# esc_board1.net
KiCad netlist of a schematic drawn in EAGLE
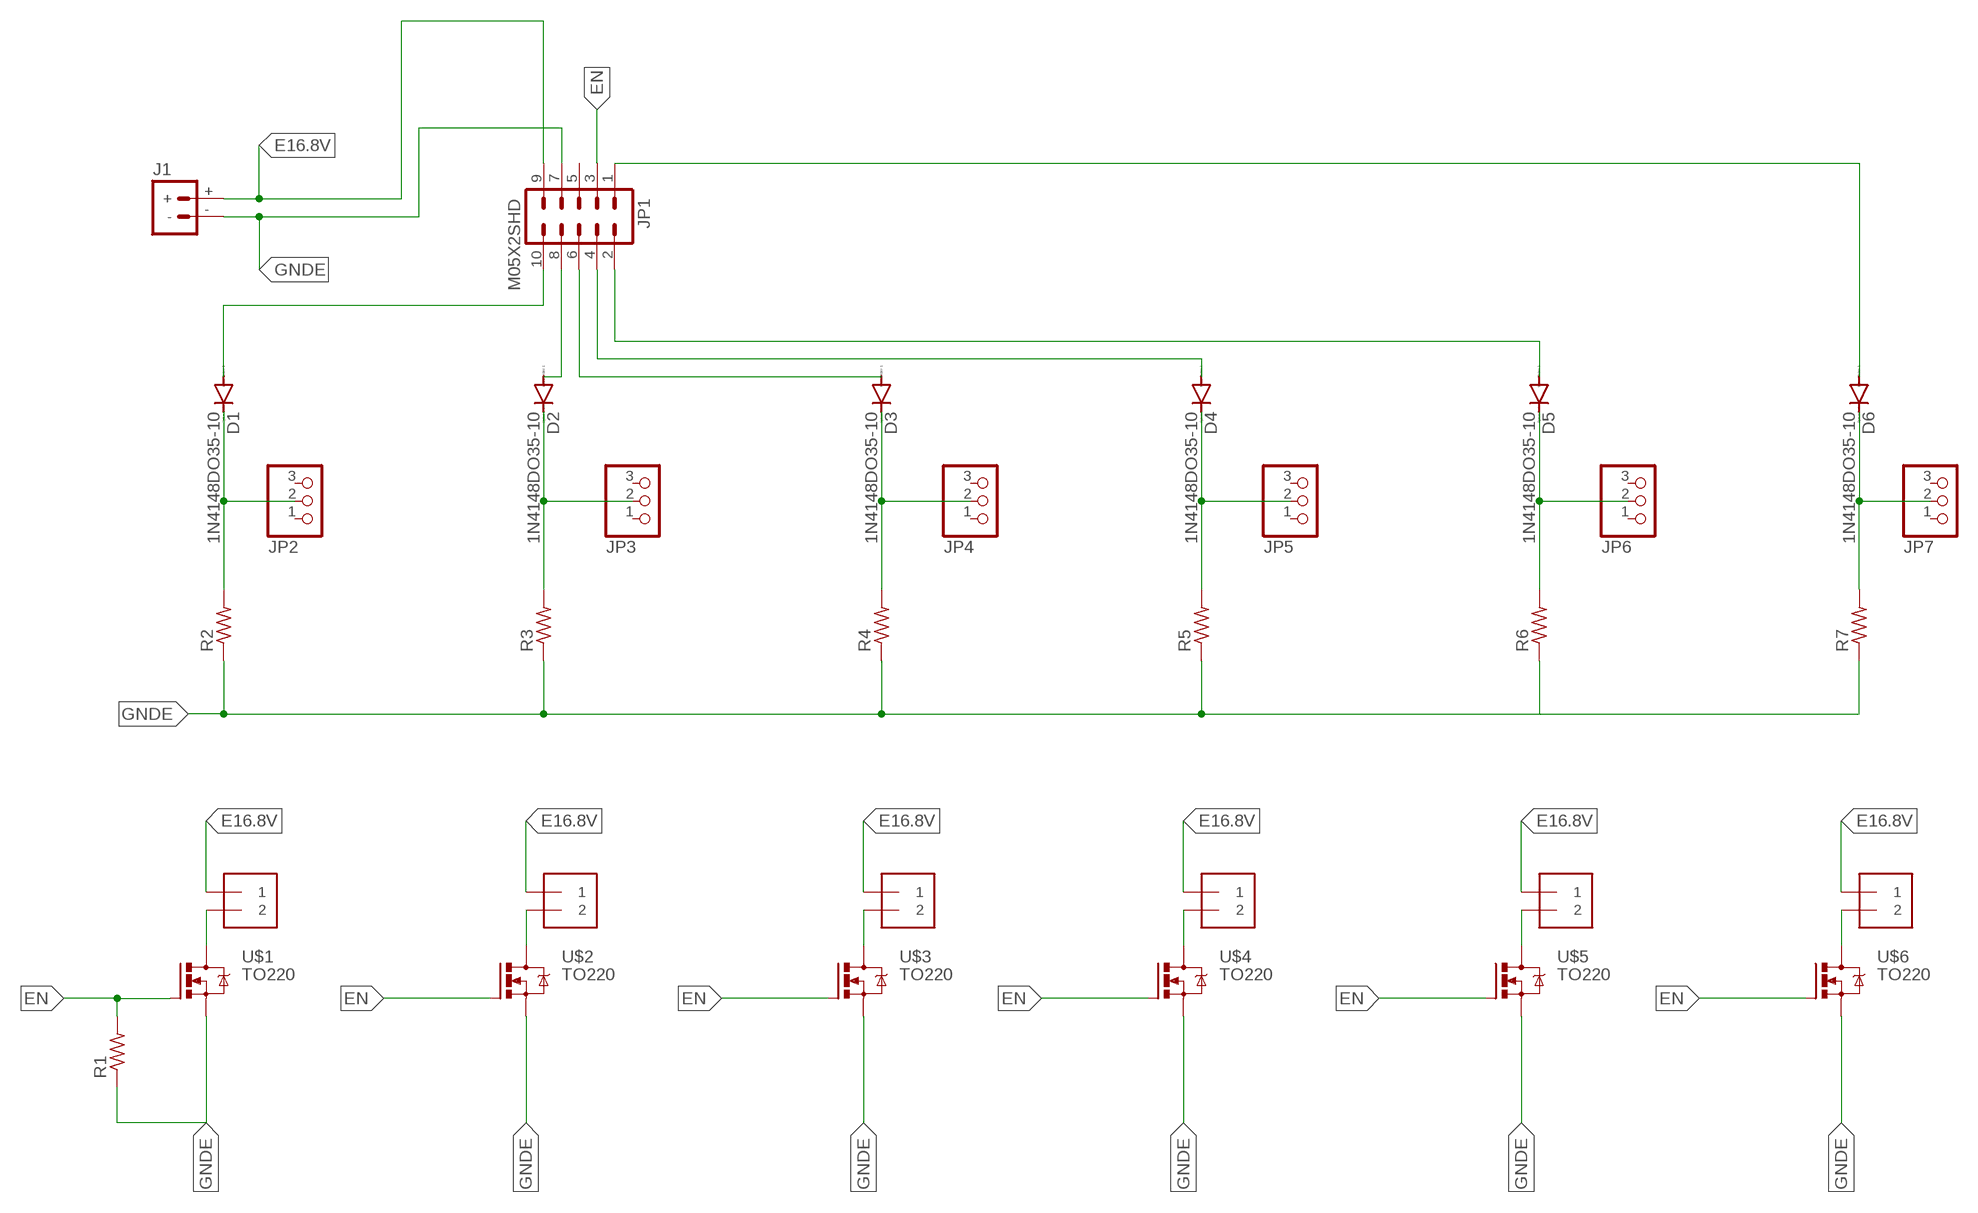
[diagram p0: schematic, sheet 1]

(export (version "E")
  (design (tool "Eeschema 10.0.6"))
  (components
    (comp (ref "D1")
      (value "1N4148DO35-10")
      (footprint "eagle-import:DO35-10")
      (libsource (lib "eagle-import") (part "1N4148DO35-10"))
    )
    (comp (ref "D2")
      (value "1N4148DO35-10")
      (footprint "eagle-import:DO35-10")
      (libsource (lib "eagle-import") (part "1N4148DO35-10"))
    )
    (comp (ref "D3")
      (value "1N4148DO35-10")
      (footprint "eagle-import:DO35-10")
      (libsource (lib "eagle-import") (part "1N4148DO35-10"))
    )
    (comp (ref "D4")
      (value "1N4148DO35-10")
      (footprint "eagle-import:DO35-10")
      (libsource (lib "eagle-import") (part "1N4148DO35-10"))
    )
    (comp (ref "D5")
      (value "1N4148DO35-10")
      (footprint "eagle-import:DO35-10")
      (libsource (lib "eagle-import") (part "1N4148DO35-10"))
    )
    (comp (ref "D6")
      (value "1N4148DO35-10")
      (footprint "eagle-import:DO35-10")
      (libsource (lib "eagle-import") (part "1N4148DO35-10"))
    )
    (comp (ref "J1")
      (value "BATTERY_CONN_DEANS")
      (footprint "eagle-import:DEANS")
      (libsource (lib "eagle-import") (part "BATTERY_CONN_DEANS"))
    )
    (comp (ref "J7")
      (value "1X2-3.5MM")
      (footprint "eagle-import:1X2-3.5MM")
      (libsource (lib "eagle-import") (part "1X2-3.5MM"))
    )
    (comp (ref "J8")
      (value "1X2-3.5MM")
      (footprint "eagle-import:1X2-3.5MM")
      (libsource (lib "eagle-import") (part "1X2-3.5MM"))
    )
    (comp (ref "J9")
      (value "1X2-3.5MM")
      (footprint "eagle-import:1X2-3.5MM")
      (libsource (lib "eagle-import") (part "1X2-3.5MM"))
    )
    (comp (ref "J10")
      (value "1X2-3.5MM")
      (footprint "eagle-import:1X2-3.5MM")
      (libsource (lib "eagle-import") (part "1X2-3.5MM"))
    )
    (comp (ref "J11")
      (value "1X2-3.5MM")
      (footprint "eagle-import:1X2-3.5MM")
      (libsource (lib "eagle-import") (part "1X2-3.5MM"))
    )
    (comp (ref "J12")
      (value "1X2-3.5MM")
      (footprint "eagle-import:1X2-3.5MM")
      (libsource (lib "eagle-import") (part "1X2-3.5MM"))
    )
    (comp (ref "JP1")
      (value "M05X2SHD")
      (footprint "eagle-import:2X5-SHROUDED")
      (libsource (lib "eagle-import") (part "M05X2SHD"))
    )
    (comp (ref "JP2")
      (value "PINHD-1X3")
      (footprint "eagle-import:1X03")
      (libsource (lib "eagle-import") (part "PINHD-1X3"))
    )
    (comp (ref "JP3")
      (value "PINHD-1X3")
      (footprint "eagle-import:1X03")
      (libsource (lib "eagle-import") (part "PINHD-1X3"))
    )
    (comp (ref "JP4")
      (value "PINHD-1X3")
      (footprint "eagle-import:1X03")
      (libsource (lib "eagle-import") (part "PINHD-1X3"))
    )
    (comp (ref "JP5")
      (value "PINHD-1X3")
      (footprint "eagle-import:1X03")
      (libsource (lib "eagle-import") (part "PINHD-1X3"))
    )
    (comp (ref "JP6")
      (value "PINHD-1X3")
      (footprint "eagle-import:1X03")
      (libsource (lib "eagle-import") (part "PINHD-1X3"))
    )
    (comp (ref "JP7")
      (value "PINHD-1X3")
      (footprint "eagle-import:1X03")
      (libsource (lib "eagle-import") (part "PINHD-1X3"))
    )
    (comp (ref "R1")
      (value "R-US_0204/7")
      (footprint "eagle-import:0204_7")
      (libsource (lib "eagle-import") (part "R-US_0204/7"))
    )
    (comp (ref "R2")
      (value "R-US_0204/7")
      (footprint "eagle-import:0204_7")
      (libsource (lib "eagle-import") (part "R-US_0204/7"))
    )
    (comp (ref "R3")
      (value "R-US_0204/7")
      (footprint "eagle-import:0204_7")
      (libsource (lib "eagle-import") (part "R-US_0204/7"))
    )
    (comp (ref "R4")
      (value "R-US_0204/7")
      (footprint "eagle-import:0204_7")
      (libsource (lib "eagle-import") (part "R-US_0204/7"))
    )
    (comp (ref "R5")
      (value "R-US_0204/7")
      (footprint "eagle-import:0204_7")
      (libsource (lib "eagle-import") (part "R-US_0204/7"))
    )
    (comp (ref "R6")
      (value "R-US_0204/7")
      (footprint "eagle-import:0204_7")
      (libsource (lib "eagle-import") (part "R-US_0204/7"))
    )
    (comp (ref "R7")
      (value "R-US_0204/7")
      (footprint "eagle-import:0204_7")
      (libsource (lib "eagle-import") (part "R-US_0204/7"))
    )
    (comp (ref "U$1")
      (value "TO220")
      (footprint "eagle-import:IRF540")
      (libsource (lib "eagle-import") (part "TO220"))
    )
    (comp (ref "U$2")
      (value "TO220")
      (footprint "eagle-import:IRF540")
      (libsource (lib "eagle-import") (part "TO220"))
    )
    (comp (ref "U$3")
      (value "TO220")
      (footprint "eagle-import:IRF540")
      (libsource (lib "eagle-import") (part "TO220"))
    )
    (comp (ref "U$4")
      (value "TO220")
      (footprint "eagle-import:IRF540")
      (libsource (lib "eagle-import") (part "TO220"))
    )
    (comp (ref "U$5")
      (value "TO220")
      (footprint "eagle-import:IRF540")
      (libsource (lib "eagle-import") (part "TO220"))
    )
    (comp (ref "U$6")
      (value "TO220")
      (footprint "eagle-import:IRF540")
      (libsource (lib "eagle-import") (part "TO220"))
    )
  )
  (nets
    (net (code "1") (name "E16.8V") (class "Default")
      (node (ref "J1") (pin "+") (pinfunction "+_+") (pintype "passive"))
      (node (ref "J10") (pin "1") (pinfunction "1_1") (pintype "passive"))
      (node (ref "J11") (pin "1") (pinfunction "1_1") (pintype "passive"))
      (node (ref "J12") (pin "1") (pinfunction "1_1") (pintype "passive"))
      (node (ref "J7") (pin "1") (pinfunction "1_1") (pintype "passive"))
      (node (ref "J8") (pin "1") (pinfunction "1_1") (pintype "passive"))
      (node (ref "J9") (pin "1") (pinfunction "1_1") (pintype "passive"))
      (node (ref "JP1") (pin "9") (pinfunction "9_9") (pintype "passive"))
    )
    (net (code "2") (name "EN") (class "Default")
      (node (ref "JP1") (pin "3") (pinfunction "3_3") (pintype "passive"))
      (node (ref "R1") (pin "2") (pinfunction "2_2") (pintype "passive"))
      (node (ref "U$1") (pin "1") (pinfunction "G_1") (pintype "passive"))
      (node (ref "U$2") (pin "1") (pinfunction "G_1") (pintype "passive"))
      (node (ref "U$3") (pin "1") (pinfunction "G_1") (pintype "passive"))
      (node (ref "U$4") (pin "1") (pinfunction "G_1") (pintype "passive"))
      (node (ref "U$5") (pin "1") (pinfunction "G_1") (pintype "passive"))
      (node (ref "U$6") (pin "1") (pinfunction "G_1") (pintype "passive"))
    )
    (net (code "3") (name "GNDE") (class "Default")
      (node (ref "J1") (pin "-") (pinfunction "-_-") (pintype "passive"))
      (node (ref "JP1") (pin "7") (pinfunction "7_7") (pintype "passive"))
      (node (ref "R1") (pin "1") (pinfunction "1_1") (pintype "passive"))
      (node (ref "R2") (pin "1") (pinfunction "1_1") (pintype "passive"))
      (node (ref "R3") (pin "1") (pinfunction "1_1") (pintype "passive"))
      (node (ref "R4") (pin "1") (pinfunction "1_1") (pintype "passive"))
      (node (ref "R5") (pin "1") (pinfunction "1_1") (pintype "passive"))
      (node (ref "R6") (pin "1") (pinfunction "1_1") (pintype "passive"))
      (node (ref "R7") (pin "1") (pinfunction "1_1") (pintype "passive"))
      (node (ref "U$1") (pin "3") (pinfunction "S_3") (pintype "passive"))
      (node (ref "U$2") (pin "3") (pinfunction "S_3") (pintype "passive"))
      (node (ref "U$3") (pin "3") (pinfunction "S_3") (pintype "passive"))
      (node (ref "U$4") (pin "3") (pinfunction "S_3") (pintype "passive"))
      (node (ref "U$5") (pin "3") (pinfunction "S_3") (pintype "passive"))
      (node (ref "U$6") (pin "3") (pinfunction "S_3") (pintype "passive"))
    )
    (net (code "4") (name "Net-(D1-PadA)") (class "Default")
      (node (ref "D1") (pin "A") (pinfunction "A_A") (pintype "passive"))
      (node (ref "JP1") (pin "10") (pinfunction "10_10") (pintype "passive"))
    )
    (net (code "5") (name "Net-(D1-PadC)") (class "Default")
      (node (ref "D1") (pin "C") (pinfunction "C_C") (pintype "passive"))
      (node (ref "JP2") (pin "2") (pinfunction "2_2") (pintype "passive"))
      (node (ref "R2") (pin "2") (pinfunction "2_2") (pintype "passive"))
    )
    (net (code "6") (name "Net-(D2-PadA)") (class "Default")
      (node (ref "D2") (pin "A") (pinfunction "A_A") (pintype "passive"))
      (node (ref "JP1") (pin "8") (pinfunction "8_8") (pintype "passive"))
    )
    (net (code "7") (name "Net-(D2-PadC)") (class "Default")
      (node (ref "D2") (pin "C") (pinfunction "C_C") (pintype "passive"))
      (node (ref "JP3") (pin "2") (pinfunction "2_2") (pintype "passive"))
      (node (ref "R3") (pin "2") (pinfunction "2_2") (pintype "passive"))
    )
    (net (code "8") (name "Net-(D3-PadA)") (class "Default")
      (node (ref "D3") (pin "A") (pinfunction "A_A") (pintype "passive"))
      (node (ref "JP1") (pin "6") (pinfunction "6_6") (pintype "passive"))
    )
    (net (code "9") (name "Net-(D3-PadC)") (class "Default")
      (node (ref "D3") (pin "C") (pinfunction "C_C") (pintype "passive"))
      (node (ref "JP4") (pin "2") (pinfunction "2_2") (pintype "passive"))
      (node (ref "R4") (pin "2") (pinfunction "2_2") (pintype "passive"))
    )
    (net (code "10") (name "Net-(D4-PadA)") (class "Default")
      (node (ref "D4") (pin "A") (pinfunction "A_A") (pintype "passive"))
      (node (ref "JP1") (pin "4") (pinfunction "4_4") (pintype "passive"))
    )
    (net (code "11") (name "Net-(D4-PadC)") (class "Default")
      (node (ref "D4") (pin "C") (pinfunction "C_C") (pintype "passive"))
      (node (ref "JP5") (pin "2") (pinfunction "2_2") (pintype "passive"))
      (node (ref "R5") (pin "2") (pinfunction "2_2") (pintype "passive"))
    )
    (net (code "12") (name "Net-(D5-PadA)") (class "Default")
      (node (ref "D5") (pin "A") (pinfunction "A_A") (pintype "passive"))
      (node (ref "JP1") (pin "2") (pinfunction "2_2") (pintype "passive"))
    )
    (net (code "13") (name "Net-(D5-PadC)") (class "Default")
      (node (ref "D5") (pin "C") (pinfunction "C_C") (pintype "passive"))
      (node (ref "JP6") (pin "2") (pinfunction "2_2") (pintype "passive"))
      (node (ref "R6") (pin "2") (pinfunction "2_2") (pintype "passive"))
    )
    (net (code "14") (name "Net-(D6-PadA)") (class "Default")
      (node (ref "D6") (pin "A") (pinfunction "A_A") (pintype "passive"))
      (node (ref "JP1") (pin "1") (pinfunction "1_1") (pintype "passive"))
    )
    (net (code "15") (name "Net-(D6-PadC)") (class "Default")
      (node (ref "D6") (pin "C") (pinfunction "C_C") (pintype "passive"))
      (node (ref "JP7") (pin "2") (pinfunction "2_2") (pintype "passive"))
      (node (ref "R7") (pin "2") (pinfunction "2_2") (pintype "passive"))
    )
    (net (code "16") (name "Net-(U$1-D)") (class "Default")
      (node (ref "J7") (pin "2") (pinfunction "2_2") (pintype "passive"))
      (node (ref "U$1") (pin "2") (pinfunction "D_2") (pintype "passive"))
    )
    (net (code "17") (name "Net-(U$2-D)") (class "Default")
      (node (ref "J8") (pin "2") (pinfunction "2_2") (pintype "passive"))
      (node (ref "U$2") (pin "2") (pinfunction "D_2") (pintype "passive"))
    )
    (net (code "18") (name "Net-(U$3-D)") (class "Default")
      (node (ref "J9") (pin "2") (pinfunction "2_2") (pintype "passive"))
      (node (ref "U$3") (pin "2") (pinfunction "D_2") (pintype "passive"))
    )
    (net (code "19") (name "Net-(U$4-D)") (class "Default")
      (node (ref "J10") (pin "2") (pinfunction "2_2") (pintype "passive"))
      (node (ref "U$4") (pin "2") (pinfunction "D_2") (pintype "passive"))
    )
    (net (code "20") (name "Net-(U$5-D)") (class "Default")
      (node (ref "J11") (pin "2") (pinfunction "2_2") (pintype "passive"))
      (node (ref "U$5") (pin "2") (pinfunction "D_2") (pintype "passive"))
    )
    (net (code "21") (name "Net-(U$6-D)") (class "Default")
      (node (ref "J12") (pin "2") (pinfunction "2_2") (pintype "passive"))
      (node (ref "U$6") (pin "2") (pinfunction "D_2") (pintype "passive"))
    )
    (net (code "22") (name "unconnected-(JP1-Pad5)") (class "Default")
      (node (ref "JP1") (pin "5") (pinfunction "5_5") (pintype "passive"))
    )
    (net (code "23") (name "unconnected-(JP2-Pad1)") (class "Default")
      (node (ref "JP2") (pin "1") (pinfunction "1_1") (pintype "passive"))
    )
    (net (code "24") (name "unconnected-(JP2-Pad3)") (class "Default")
      (node (ref "JP2") (pin "3") (pinfunction "3_3") (pintype "passive"))
    )
    (net (code "25") (name "unconnected-(JP3-Pad1)") (class "Default")
      (node (ref "JP3") (pin "1") (pinfunction "1_1") (pintype "passive"))
    )
    (net (code "26") (name "unconnected-(JP3-Pad3)") (class "Default")
      (node (ref "JP3") (pin "3") (pinfunction "3_3") (pintype "passive"))
    )
    (net (code "27") (name "unconnected-(JP4-Pad1)") (class "Default")
      (node (ref "JP4") (pin "1") (pinfunction "1_1") (pintype "passive"))
    )
    (net (code "28") (name "unconnected-(JP4-Pad3)") (class "Default")
      (node (ref "JP4") (pin "3") (pinfunction "3_3") (pintype "passive"))
    )
    (net (code "29") (name "unconnected-(JP5-Pad1)") (class "Default")
      (node (ref "JP5") (pin "1") (pinfunction "1_1") (pintype "passive"))
    )
    (net (code "30") (name "unconnected-(JP5-Pad3)") (class "Default")
      (node (ref "JP5") (pin "3") (pinfunction "3_3") (pintype "passive"))
    )
    (net (code "31") (name "unconnected-(JP6-Pad1)") (class "Default")
      (node (ref "JP6") (pin "1") (pinfunction "1_1") (pintype "passive"))
    )
    (net (code "32") (name "unconnected-(JP6-Pad3)") (class "Default")
      (node (ref "JP6") (pin "3") (pinfunction "3_3") (pintype "passive"))
    )
    (net (code "33") (name "unconnected-(JP7-Pad1)") (class "Default")
      (node (ref "JP7") (pin "1") (pinfunction "1_1") (pintype "passive"))
    )
    (net (code "34") (name "unconnected-(JP7-Pad3)") (class "Default")
      (node (ref "JP7") (pin "3") (pinfunction "3_3") (pintype "passive"))
    )
  )
)
